# working.net
KiCad netlist of a schematic drawn in EAGLE
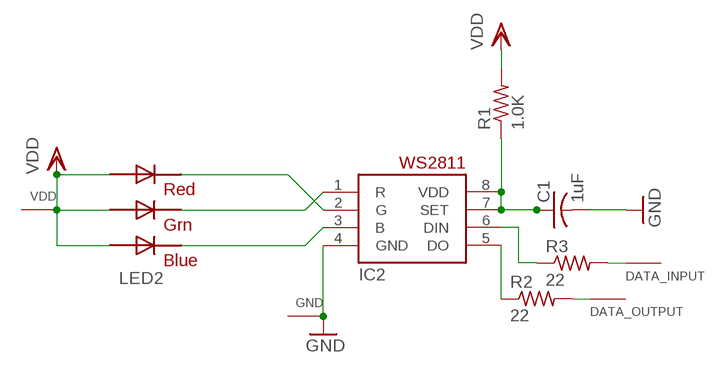
[diagram p0: schematic, sheet 1]

(export (version "E")
  (design (tool "Eeschema 10.0.6"))
  (components
    (comp (ref "C1")
      (value "1uF")
      (footprint "eagle-import:C0805K")
      (libsource (lib "eagle-import") (part "C-USC0805K"))
    )
    (comp (ref "DATA_INPUT")
      (value "SEWTAP0.5IN")
      (footprint "eagle-import:SEWINGTAP_0.5")
      (libsource (lib "eagle-import") (part "SEWTAP0.5IN"))
    )
    (comp (ref "DATA_OUTPUT")
      (value "SEWTAP0.5IN")
      (footprint "eagle-import:SEWINGTAP_0.5")
      (libsource (lib "eagle-import") (part "SEWTAP0.5IN"))
    )
    (comp (ref "GND")
      (value "SEWTAP0.5IN")
      (footprint "eagle-import:SEWINGTAP_0.5")
      (libsource (lib "eagle-import") (part "SEWTAP0.5IN"))
    )
    (comp (ref "IC2")
      (value "WS2811-SOP8")
      (footprint "eagle-import:SO08-SKINNYPADS")
      (libsource (lib "eagle-import") (part "WS2811-SOP8"))
    )
    (comp (ref "LED2")
      (value "RGBLED5050")
      (footprint "eagle-import:RGBLED5050")
      (libsource (lib "eagle-import") (part "RGBLED5050"))
    )
    (comp (ref "R1")
      (value "1.0K")
      (footprint "eagle-import:R0805")
      (libsource (lib "eagle-import") (part "R-US_R0805"))
    )
    (comp (ref "R2")
      (value "22")
      (footprint "eagle-import:R0805")
      (libsource (lib "eagle-import") (part "R-US_R0805"))
    )
    (comp (ref "R3")
      (value "22")
      (footprint "eagle-import:R0805")
      (libsource (lib "eagle-import") (part "R-US_R0805"))
    )
    (comp (ref "VDD")
      (value "SEWTAP0.5IN")
      (footprint "eagle-import:SEWINGTAP_0.5")
      (libsource (lib "eagle-import") (part "SEWTAP0.5IN"))
    )
  )
  (nets
    (net (code "1") (name "GND") (class "Default")
      (node (ref "C1") (pin "2") (pinfunction "2_2") (pintype "passive"))
      (node (ref "GND") (pin "TAP") (pinfunction "SEW_TAP") (pintype "bidirectional"))
      (node (ref "IC2") (pin "4") (pinfunction "GND_4") (pintype "power_in"))
    )
    (net (code "2") (name "Net-(DATA_INPUT-SEW)") (class "Default")
      (node (ref "DATA_INPUT") (pin "TAP") (pinfunction "SEW_TAP") (pintype "bidirectional"))
      (node (ref "R3") (pin "2") (pinfunction "2_2") (pintype "passive"))
    )
    (net (code "3") (name "Net-(DATA_OUTPUT-SEW)") (class "Default")
      (node (ref "DATA_OUTPUT") (pin "TAP") (pinfunction "SEW_TAP") (pintype "bidirectional"))
      (node (ref "R2") (pin "2") (pinfunction "2_2") (pintype "passive"))
    )
    (net (code "4") (name "Net-(IC2-B)") (class "Default")
      (node (ref "IC2") (pin "3") (pinfunction "B_3") (pintype "open_collector"))
      (node (ref "LED2") (pin "4") (pinfunction "BLUE_C_4") (pintype "bidirectional"))
    )
    (net (code "5") (name "Net-(IC2-DIN)") (class "Default")
      (node (ref "IC2") (pin "6") (pinfunction "DIN_6") (pintype "input"))
      (node (ref "R3") (pin "1") (pinfunction "1_1") (pintype "passive"))
    )
    (net (code "6") (name "Net-(IC2-DO)") (class "Default")
      (node (ref "IC2") (pin "5") (pinfunction "DO_5") (pintype "output"))
      (node (ref "R2") (pin "1") (pinfunction "1_1") (pintype "passive"))
    )
    (net (code "7") (name "Net-(IC2-G)") (class "Default")
      (node (ref "IC2") (pin "2") (pinfunction "G_2") (pintype "open_collector"))
      (node (ref "LED2") (pin "5") (pinfunction "RED_C_5") (pintype "bidirectional"))
    )
    (net (code "8") (name "Net-(IC2-R)") (class "Default")
      (node (ref "IC2") (pin "1") (pinfunction "R_1") (pintype "open_collector"))
      (node (ref "LED2") (pin "6") (pinfunction "GREEN_C_6") (pintype "bidirectional"))
    )
    (net (code "9") (name "Net-(IC2-SET)") (class "Default")
      (node (ref "C1") (pin "1") (pinfunction "1_1") (pintype "passive"))
      (node (ref "IC2") (pin "7") (pinfunction "SET_7") (pintype "input"))
      (node (ref "IC2") (pin "8") (pinfunction "VDD_8") (pintype "power_in"))
      (node (ref "R1") (pin "1") (pinfunction "1_1") (pintype "passive"))
    )
    (net (code "10") (name "VDD") (class "Default")
      (node (ref "LED2") (pin "1") (pinfunction "GREEN_A_1") (pintype "bidirectional"))
      (node (ref "LED2") (pin "2") (pinfunction "RED_A_2") (pintype "bidirectional"))
      (node (ref "LED2") (pin "3") (pinfunction "BLUE_A_3") (pintype "bidirectional"))
      (node (ref "R1") (pin "2") (pinfunction "2_2") (pintype "passive"))
      (node (ref "VDD") (pin "TAP") (pinfunction "SEW_TAP") (pintype "bidirectional"))
    )
  )
)
